# MicroNovaDisplayRevX3.net
KiCad netlist of a schematic drawn in EAGLE
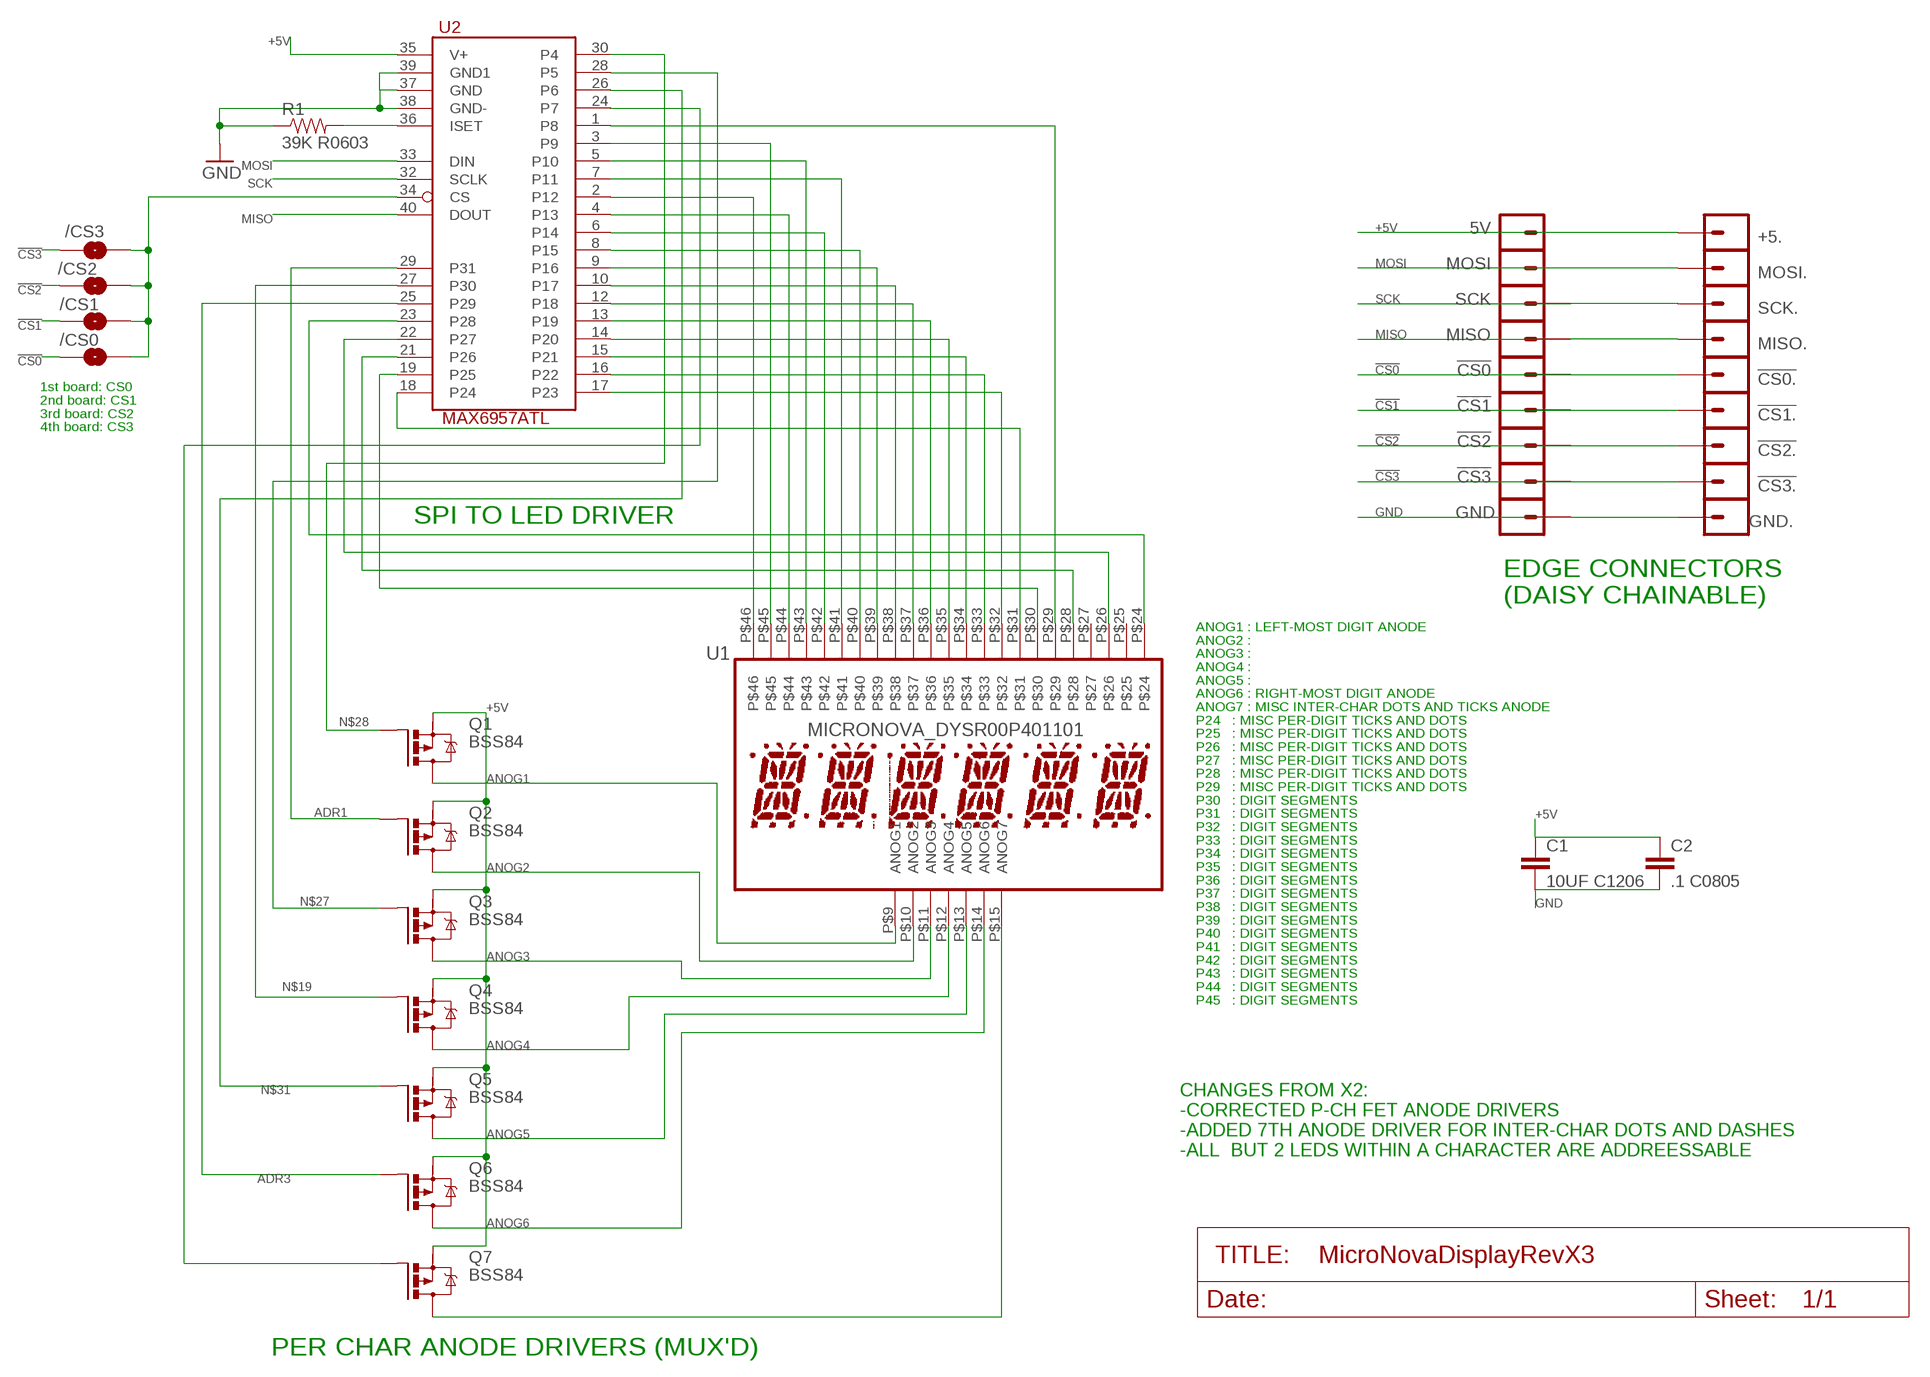
[diagram p0: schematic, sheet 1]

(export (version "E")
  (design (tool "Eeschema 10.0.6"))
  (components
    (comp (ref "!CS0")
      (value "M01")
      (footprint "eagle-import:1X01_SMT_2MM")
      (libsource (lib "eagle-import") (part "M01"))
    )
    (comp (ref "!CS0.")
      (value "M01")
      (footprint "eagle-import:1X01_SMT_2MM")
      (libsource (lib "eagle-import") (part "M01"))
    )
    (comp (ref "!CS1")
      (value "M01")
      (footprint "eagle-import:1X01_SMT_2MM")
      (libsource (lib "eagle-import") (part "M01"))
    )
    (comp (ref "!CS1.")
      (value "M01")
      (footprint "eagle-import:1X01_SMT_2MM")
      (libsource (lib "eagle-import") (part "M01"))
    )
    (comp (ref "!CS2")
      (value "M01")
      (footprint "eagle-import:1X01_SMT_2MM")
      (libsource (lib "eagle-import") (part "M01"))
    )
    (comp (ref "!CS2.")
      (value "M01")
      (footprint "eagle-import:1X01_SMT_2MM")
      (libsource (lib "eagle-import") (part "M01"))
    )
    (comp (ref "!CS3")
      (value "M01")
      (footprint "eagle-import:1X01_SMT_2MM")
      (libsource (lib "eagle-import") (part "M01"))
    )
    (comp (ref "!CS3.")
      (value "M01")
      (footprint "eagle-import:1X01_SMT_2MM")
      (libsource (lib "eagle-import") (part "M01"))
    )
    (comp (ref "+5.")
      (value "M01")
      (footprint "eagle-import:1X01_SMT_2MM")
      (libsource (lib "eagle-import") (part "M01"))
    )
    (comp (ref "/CS0")
      (value "JUMPER-PAD-2-NOYES_SILK")
      (footprint "eagle-import:PAD-JUMPER-2-NO_YES_SILK")
      (libsource (lib "eagle-import") (part "JUMPER-PAD-2-NOYES_SILK"))
    )
    (comp (ref "/CS1")
      (value "JUMPER-PAD-2-NOYES_SILK")
      (footprint "eagle-import:PAD-JUMPER-2-NO_YES_SILK")
      (libsource (lib "eagle-import") (part "JUMPER-PAD-2-NOYES_SILK"))
    )
    (comp (ref "/CS2")
      (value "JUMPER-PAD-2-NOYES_SILK")
      (footprint "eagle-import:PAD-JUMPER-2-NO_YES_SILK")
      (libsource (lib "eagle-import") (part "JUMPER-PAD-2-NOYES_SILK"))
    )
    (comp (ref "/CS3")
      (value "JUMPER-PAD-2-NOYES_SILK")
      (footprint "eagle-import:PAD-JUMPER-2-NO_YES_SILK")
      (libsource (lib "eagle-import") (part "JUMPER-PAD-2-NOYES_SILK"))
    )
    (comp (ref "5V")
      (value "M01")
      (footprint "eagle-import:1X01_SMT_2MM")
      (libsource (lib "eagle-import") (part "M01"))
    )
    (comp (ref "C1")
      (value "10UF C1206")
      (footprint "eagle-import:1206")
      (libsource (lib "eagle-import") (part "CAP1206"))
    )
    (comp (ref "C2")
      (value ".1 C0805")
      (footprint "eagle-import:0805")
      (libsource (lib "eagle-import") (part "CAP0805"))
    )
    (comp (ref "GND")
      (value "M01")
      (footprint "eagle-import:1X01_SMT_2MM")
      (libsource (lib "eagle-import") (part "M01"))
    )
    (comp (ref "GND.")
      (value "M01")
      (footprint "eagle-import:1X01_SMT_2MM")
      (libsource (lib "eagle-import") (part "M01"))
    )
    (comp (ref "MISO")
      (value "M01")
      (footprint "eagle-import:1X01_SMT_2MM")
      (libsource (lib "eagle-import") (part "M01"))
    )
    (comp (ref "MISO.")
      (value "M01")
      (footprint "eagle-import:1X01_SMT_2MM")
      (libsource (lib "eagle-import") (part "M01"))
    )
    (comp (ref "MOSI")
      (value "M01")
      (footprint "eagle-import:1X01_SMT_2MM")
      (libsource (lib "eagle-import") (part "M01"))
    )
    (comp (ref "MOSI.")
      (value "M01")
      (footprint "eagle-import:1X01_SMT_2MM")
      (libsource (lib "eagle-import") (part "M01"))
    )
    (comp (ref "Q1")
      (value "BSS84")
      (footprint "eagle-import:SOT23-3")
      (libsource (lib "eagle-import") (part "MOSFET-PCHANNELGATE1_SOURCE2_DRAIN3"))
    )
    (comp (ref "Q2")
      (value "BSS84")
      (footprint "eagle-import:SOT23-3")
      (libsource (lib "eagle-import") (part "MOSFET-PCHANNELGATE1_SOURCE2_DRAIN3"))
    )
    (comp (ref "Q3")
      (value "BSS84")
      (footprint "eagle-import:SOT23-3")
      (libsource (lib "eagle-import") (part "MOSFET-PCHANNELGATE1_SOURCE2_DRAIN3"))
    )
    (comp (ref "Q4")
      (value "BSS84")
      (footprint "eagle-import:SOT23-3")
      (libsource (lib "eagle-import") (part "MOSFET-PCHANNELGATE1_SOURCE2_DRAIN3"))
    )
    (comp (ref "Q5")
      (value "BSS84")
      (footprint "eagle-import:SOT23-3")
      (libsource (lib "eagle-import") (part "MOSFET-PCHANNELGATE1_SOURCE2_DRAIN3"))
    )
    (comp (ref "Q6")
      (value "BSS84")
      (footprint "eagle-import:SOT23-3")
      (libsource (lib "eagle-import") (part "MOSFET-PCHANNELGATE1_SOURCE2_DRAIN3"))
    )
    (comp (ref "Q7")
      (value "BSS84")
      (footprint "eagle-import:SOT23-3")
      (libsource (lib "eagle-import") (part "MOSFET-PCHANNELGATE1_SOURCE2_DRAIN3"))
    )
    (comp (ref "R1")
      (value "39K R0603")
      (footprint "eagle-import:0603")
      (libsource (lib "eagle-import") (part "RES0603"))
    )
    (comp (ref "SCK")
      (value "M01")
      (footprint "eagle-import:1X01_SMT_2MM")
      (libsource (lib "eagle-import") (part "M01"))
    )
    (comp (ref "SCK.")
      (value "M01")
      (footprint "eagle-import:1X01_SMT_2MM")
      (libsource (lib "eagle-import") (part "M01"))
    )
    (comp (ref "U1")
      (value "MICRONOVA_DYSR00P401101")
      (footprint "eagle-import:ALPHANUMERIC")
      (libsource (lib "eagle-import") (part "MICRONOVA_DYSR00P401101"))
    )
    (comp (ref "U2")
      (value "MAX6957ATL")
      (footprint "eagle-import:TQFP40")
      (libsource (lib "eagle-import") (part "MAX6957ATL"))
    )
  )
  (nets
    (net (code "1") (name "/+5V") (class "Default")
      (node (ref "+5.") (pin "P$1") (pinfunction "1_P$1") (pintype "passive"))
      (node (ref "5V") (pin "P$1") (pinfunction "1_P$1") (pintype "passive"))
      (node (ref "C1") (pin "1") (pinfunction "1_1") (pintype "passive"))
      (node (ref "C2") (pin "1") (pinfunction "1_1") (pintype "passive"))
      (node (ref "Q1") (pin "2") (pinfunction "1S_2") (pintype "bidirectional"))
      (node (ref "Q2") (pin "2") (pinfunction "1S_2") (pintype "bidirectional"))
      (node (ref "Q3") (pin "2") (pinfunction "1S_2") (pintype "bidirectional"))
      (node (ref "Q4") (pin "2") (pinfunction "1S_2") (pintype "bidirectional"))
      (node (ref "Q5") (pin "2") (pinfunction "1S_2") (pintype "bidirectional"))
      (node (ref "Q6") (pin "2") (pinfunction "1S_2") (pintype "bidirectional"))
      (node (ref "Q7") (pin "2") (pinfunction "1S_2") (pintype "bidirectional"))
      (node (ref "U2") (pin "35") (pinfunction "V+_35") (pintype "bidirectional"))
    )
    (net (code "2") (name "/ADR1") (class "Default")
      (node (ref "Q2") (pin "1") (pinfunction "2G_1") (pintype "bidirectional"))
      (node (ref "U2") (pin "29") (pinfunction "P31_29") (pintype "bidirectional"))
    )
    (net (code "3") (name "/ADR3") (class "Default")
      (node (ref "Q6") (pin "1") (pinfunction "2G_1") (pintype "bidirectional"))
      (node (ref "U2") (pin "25") (pinfunction "P29_25") (pintype "bidirectional"))
    )
    (net (code "4") (name "/ANOG1") (class "Default")
      (node (ref "Q1") (pin "3") (pinfunction "3D_3") (pintype "bidirectional"))
      (node (ref "U1") (pin "P$9") (pinfunction "ANOG1_P$9") (pintype "bidirectional"))
    )
    (net (code "5") (name "/ANOG2") (class "Default")
      (node (ref "Q2") (pin "3") (pinfunction "3D_3") (pintype "bidirectional"))
      (node (ref "U1") (pin "P$10") (pinfunction "ANOG2_P$10") (pintype "bidirectional"))
    )
    (net (code "6") (name "/ANOG3") (class "Default")
      (node (ref "Q3") (pin "3") (pinfunction "3D_3") (pintype "bidirectional"))
      (node (ref "U1") (pin "P$11") (pinfunction "ANOG3_P$11") (pintype "bidirectional"))
    )
    (net (code "7") (name "/ANOG4") (class "Default")
      (node (ref "Q4") (pin "3") (pinfunction "3D_3") (pintype "bidirectional"))
      (node (ref "U1") (pin "P$12") (pinfunction "ANOG4_P$12") (pintype "bidirectional"))
    )
    (net (code "8") (name "/ANOG5") (class "Default")
      (node (ref "Q5") (pin "3") (pinfunction "3D_3") (pintype "bidirectional"))
      (node (ref "U1") (pin "P$13") (pinfunction "ANOG5_P$13") (pintype "bidirectional"))
    )
    (net (code "9") (name "/ANOG6") (class "Default")
      (node (ref "Q6") (pin "3") (pinfunction "3D_3") (pintype "bidirectional"))
      (node (ref "U1") (pin "P$14") (pinfunction "ANOG6_P$14") (pintype "bidirectional"))
    )
    (net (code "10") (name "/MISO") (class "Default")
      (node (ref "MISO") (pin "P$1") (pinfunction "1_P$1") (pintype "passive"))
      (node (ref "MISO.") (pin "P$1") (pinfunction "1_P$1") (pintype "passive"))
      (node (ref "U2") (pin "40") (pinfunction "DOUT_40") (pintype "bidirectional"))
    )
    (net (code "11") (name "/MOSI") (class "Default")
      (node (ref "MOSI") (pin "P$1") (pinfunction "1_P$1") (pintype "passive"))
      (node (ref "MOSI.") (pin "P$1") (pinfunction "1_P$1") (pintype "passive"))
      (node (ref "U2") (pin "33") (pinfunction "DIN_33") (pintype "bidirectional"))
    )
    (net (code "12") (name "/N$19") (class "Default")
      (node (ref "Q4") (pin "1") (pinfunction "2G_1") (pintype "bidirectional"))
      (node (ref "U2") (pin "27") (pinfunction "P30_27") (pintype "bidirectional"))
    )
    (net (code "13") (name "/N$27") (class "Default")
      (node (ref "Q3") (pin "1") (pinfunction "2G_1") (pintype "bidirectional"))
      (node (ref "U2") (pin "28") (pinfunction "P5_28") (pintype "bidirectional"))
    )
    (net (code "14") (name "/N$28") (class "Default")
      (node (ref "Q1") (pin "1") (pinfunction "2G_1") (pintype "bidirectional"))
      (node (ref "U2") (pin "30") (pinfunction "P4_30") (pintype "bidirectional"))
    )
    (net (code "15") (name "/N$31") (class "Default")
      (node (ref "Q5") (pin "1") (pinfunction "2G_1") (pintype "bidirectional"))
      (node (ref "U2") (pin "26") (pinfunction "P6_26") (pintype "bidirectional"))
    )
    (net (code "16") (name "/SCK") (class "Default")
      (node (ref "SCK") (pin "P$1") (pinfunction "1_P$1") (pintype "passive"))
      (node (ref "SCK.") (pin "P$1") (pinfunction "1_P$1") (pintype "passive"))
      (node (ref "U2") (pin "32") (pinfunction "SCLK_32") (pintype "bidirectional"))
    )
    (net (code "17") (name "/~{CS0}") (class "Default")
      (node (ref "!CS0") (pin "P$1") (pinfunction "1_P$1") (pintype "passive"))
      (node (ref "!CS0.") (pin "P$1") (pinfunction "1_P$1") (pintype "passive"))
      (node (ref "/CS0") (pin "1") (pinfunction "1_1") (pintype "passive"))
    )
    (net (code "18") (name "/~{CS1}") (class "Default")
      (node (ref "!CS1") (pin "P$1") (pinfunction "1_P$1") (pintype "passive"))
      (node (ref "!CS1.") (pin "P$1") (pinfunction "1_P$1") (pintype "passive"))
      (node (ref "/CS1") (pin "1") (pinfunction "1_1") (pintype "passive"))
    )
    (net (code "19") (name "/~{CS2}") (class "Default")
      (node (ref "!CS2") (pin "P$1") (pinfunction "1_P$1") (pintype "passive"))
      (node (ref "!CS2.") (pin "P$1") (pinfunction "1_P$1") (pintype "passive"))
      (node (ref "/CS2") (pin "1") (pinfunction "1_1") (pintype "passive"))
    )
    (net (code "20") (name "/~{CS3}") (class "Default")
      (node (ref "!CS3") (pin "P$1") (pinfunction "1_P$1") (pintype "passive"))
      (node (ref "!CS3.") (pin "P$1") (pinfunction "1_P$1") (pintype "passive"))
      (node (ref "/CS3") (pin "1") (pinfunction "1_1") (pintype "passive"))
    )
    (net (code "21") (name "GND") (class "Default")
      (node (ref "C1") (pin "2") (pinfunction "2_2") (pintype "passive"))
      (node (ref "C2") (pin "2") (pinfunction "2_2") (pintype "passive"))
      (node (ref "GND") (pin "P$1") (pinfunction "1_P$1") (pintype "passive"))
      (node (ref "GND.") (pin "P$1") (pinfunction "1_P$1") (pintype "passive"))
      (node (ref "R1") (pin "1") (pinfunction "1_1") (pintype "passive"))
      (node (ref "U2") (pin "37") (pinfunction "GND_37") (pintype "bidirectional"))
      (node (ref "U2") (pin "38") (pinfunction "GND-_38") (pintype "bidirectional"))
      (node (ref "U2") (pin "39") (pinfunction "GND1_39") (pintype "bidirectional"))
    )
    (net (code "22") (name "Net-(Q7-2G)") (class "Default")
      (node (ref "Q7") (pin "1") (pinfunction "2G_1") (pintype "bidirectional"))
      (node (ref "U2") (pin "24") (pinfunction "P7_24") (pintype "bidirectional"))
    )
    (net (code "23") (name "Net-(Q7-3D)") (class "Default")
      (node (ref "Q7") (pin "3") (pinfunction "3D_3") (pintype "bidirectional"))
      (node (ref "U1") (pin "P$15") (pinfunction "ANOG7_P$15") (pintype "bidirectional"))
    )
    (net (code "24") (name "Net-(U2-CS)") (class "Default")
      (node (ref "/CS0") (pin "2") (pinfunction "2_2") (pintype "passive"))
      (node (ref "/CS1") (pin "2") (pinfunction "2_2") (pintype "passive"))
      (node (ref "/CS2") (pin "2") (pinfunction "2_2") (pintype "passive"))
      (node (ref "/CS3") (pin "2") (pinfunction "2_2") (pintype "passive"))
      (node (ref "U2") (pin "34") (pinfunction "CS_34") (pintype "bidirectional"))
    )
    (net (code "25") (name "Net-(U2-ISET)") (class "Default")
      (node (ref "R1") (pin "2") (pinfunction "2_2") (pintype "passive"))
      (node (ref "U2") (pin "36") (pinfunction "ISET_36") (pintype "bidirectional"))
    )
    (net (code "26") (name "Net-(U2-P8)") (class "Default")
      (node (ref "U1") (pin "P$29") (pinfunction "P$29_P$29") (pintype "bidirectional"))
      (node (ref "U2") (pin "1") (pinfunction "P8_1") (pintype "bidirectional"))
    )
    (net (code "27") (name "Net-(U2-P9)") (class "Default")
      (node (ref "U1") (pin "P$45") (pinfunction "P$45_P$45") (pintype "bidirectional"))
      (node (ref "U2") (pin "3") (pinfunction "P9_3") (pintype "bidirectional"))
    )
    (net (code "28") (name "Net-(U2-P10)") (class "Default")
      (node (ref "U1") (pin "P$43") (pinfunction "P$43_P$43") (pintype "bidirectional"))
      (node (ref "U2") (pin "5") (pinfunction "P10_5") (pintype "bidirectional"))
    )
    (net (code "29") (name "Net-(U2-P11)") (class "Default")
      (node (ref "U1") (pin "P$41") (pinfunction "P$41_P$41") (pintype "bidirectional"))
      (node (ref "U2") (pin "7") (pinfunction "P11_7") (pintype "bidirectional"))
    )
    (net (code "30") (name "Net-(U2-P12)") (class "Default")
      (node (ref "U1") (pin "P$46") (pinfunction "P$46_P$46") (pintype "bidirectional"))
      (node (ref "U2") (pin "2") (pinfunction "P12_2") (pintype "bidirectional"))
    )
    (net (code "31") (name "Net-(U2-P13)") (class "Default")
      (node (ref "U1") (pin "P$44") (pinfunction "P$44_P$44") (pintype "bidirectional"))
      (node (ref "U2") (pin "4") (pinfunction "P13_4") (pintype "bidirectional"))
    )
    (net (code "32") (name "Net-(U2-P14)") (class "Default")
      (node (ref "U1") (pin "P$42") (pinfunction "P$42_P$42") (pintype "bidirectional"))
      (node (ref "U2") (pin "6") (pinfunction "P14_6") (pintype "bidirectional"))
    )
    (net (code "33") (name "Net-(U2-P15)") (class "Default")
      (node (ref "U1") (pin "P$40") (pinfunction "P$40_P$40") (pintype "bidirectional"))
      (node (ref "U2") (pin "8") (pinfunction "P15_8") (pintype "bidirectional"))
    )
    (net (code "34") (name "Net-(U2-P16)") (class "Default")
      (node (ref "U1") (pin "P$39") (pinfunction "P$39_P$39") (pintype "bidirectional"))
      (node (ref "U2") (pin "9") (pinfunction "P16_9") (pintype "bidirectional"))
    )
    (net (code "35") (name "Net-(U2-P17)") (class "Default")
      (node (ref "U1") (pin "P$38") (pinfunction "P$38_P$38") (pintype "bidirectional"))
      (node (ref "U2") (pin "10") (pinfunction "P17_10") (pintype "bidirectional"))
    )
    (net (code "36") (name "Net-(U2-P18)") (class "Default")
      (node (ref "U1") (pin "P$37") (pinfunction "P$37_P$37") (pintype "bidirectional"))
      (node (ref "U2") (pin "12") (pinfunction "P18_12") (pintype "bidirectional"))
    )
    (net (code "37") (name "Net-(U2-P19)") (class "Default")
      (node (ref "U1") (pin "P$36") (pinfunction "P$36_P$36") (pintype "bidirectional"))
      (node (ref "U2") (pin "13") (pinfunction "P19_13") (pintype "bidirectional"))
    )
    (net (code "38") (name "Net-(U2-P20)") (class "Default")
      (node (ref "U1") (pin "P$35") (pinfunction "P$35_P$35") (pintype "bidirectional"))
      (node (ref "U2") (pin "14") (pinfunction "P20_14") (pintype "bidirectional"))
    )
    (net (code "39") (name "Net-(U2-P21)") (class "Default")
      (node (ref "U1") (pin "P$34") (pinfunction "P$34_P$34") (pintype "bidirectional"))
      (node (ref "U2") (pin "15") (pinfunction "P21_15") (pintype "bidirectional"))
    )
    (net (code "40") (name "Net-(U2-P22)") (class "Default")
      (node (ref "U1") (pin "P$33") (pinfunction "P$33_P$33") (pintype "bidirectional"))
      (node (ref "U2") (pin "16") (pinfunction "P22_16") (pintype "bidirectional"))
    )
    (net (code "41") (name "Net-(U2-P23)") (class "Default")
      (node (ref "U1") (pin "P$32") (pinfunction "P$32_P$32") (pintype "bidirectional"))
      (node (ref "U2") (pin "17") (pinfunction "P23_17") (pintype "bidirectional"))
    )
    (net (code "42") (name "Net-(U2-P24)") (class "Default")
      (node (ref "U1") (pin "P$31") (pinfunction "P$31_P$31") (pintype "bidirectional"))
      (node (ref "U2") (pin "18") (pinfunction "P24_18") (pintype "bidirectional"))
    )
    (net (code "43") (name "Net-(U2-P25)") (class "Default")
      (node (ref "U1") (pin "P$30") (pinfunction "P$30_P$30") (pintype "bidirectional"))
      (node (ref "U2") (pin "19") (pinfunction "P25_19") (pintype "bidirectional"))
    )
    (net (code "44") (name "Net-(U2-P26)") (class "Default")
      (node (ref "U1") (pin "P$28") (pinfunction "P$28_P$28") (pintype "bidirectional"))
      (node (ref "U2") (pin "21") (pinfunction "P26_21") (pintype "bidirectional"))
    )
    (net (code "45") (name "Net-(U2-P27)") (class "Default")
      (node (ref "U1") (pin "P$26") (pinfunction "P$26_P$26") (pintype "bidirectional"))
      (node (ref "U2") (pin "22") (pinfunction "P27_22") (pintype "bidirectional"))
    )
    (net (code "46") (name "Net-(U2-P28)") (class "Default")
      (node (ref "U1") (pin "P$24") (pinfunction "P$24_P$24") (pintype "bidirectional"))
      (node (ref "U2") (pin "23") (pinfunction "P28_23") (pintype "bidirectional"))
    )
    (net (code "47") (name "unconnected-(U1-PadP$25)") (class "Default")
      (node (ref "U1") (pin "P$25") (pinfunction "P$25_P$25") (pintype "bidirectional"))
    )
    (net (code "48") (name "unconnected-(U1-PadP$27)") (class "Default")
      (node (ref "U1") (pin "P$27") (pinfunction "P$27_P$27") (pintype "bidirectional"))
    )
  )
)
